# buff_n_Blend.net
KiCad netlist of a schematic drawn in EAGLE
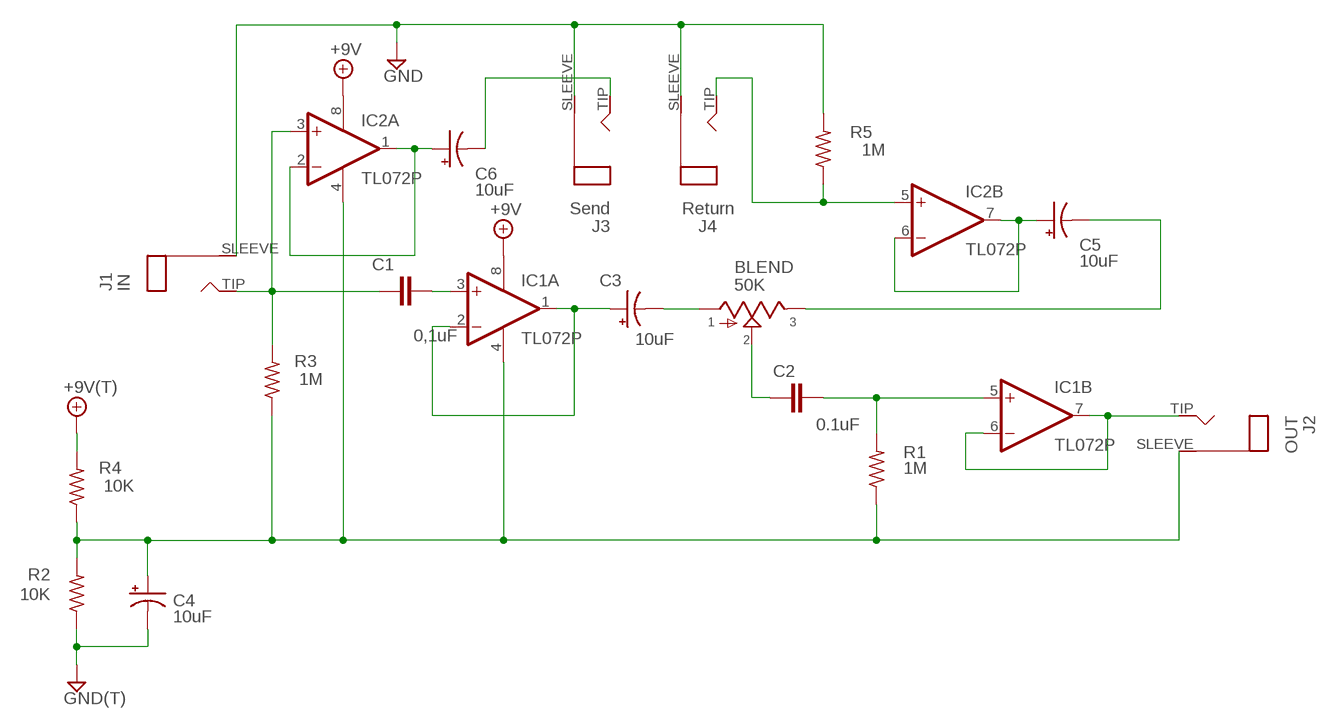
[diagram p0: schematic, sheet 1]

(export (version "E")
  (design (tool "Eeschema 10.0.6"))
  (components
    (comp (ref "+9V1")
      (value "+9V(T)")
      (footprint "eagle-import:SQUARE")
      (libsource (lib "eagle-import") (part "+9V(T)"))
    )
    (comp (ref "BLEND")
      (value "50K")
      (footprint "eagle-import:16MM")
      (libsource (lib "eagle-import") (part "POT16MM"))
    )
    (comp (ref "C1")
      (value "0,1uF")
      (footprint "eagle-import:070X030_4")
      (libsource (lib "eagle-import") (part "070X0304"))
    )
    (comp (ref "C2")
      (value "0.1uF")
      (footprint "eagle-import:070X030_4")
      (libsource (lib "eagle-import") (part "070X0304"))
    )
    (comp (ref "C3")
      (value "10uF")
      (footprint "eagle-import:063_025_3")
      (libsource (lib "eagle-import") (part "0633"))
    )
    (comp (ref "C4")
      (value "10uF")
      (footprint "eagle-import:063_025_3")
      (libsource (lib "eagle-import") (part "0633"))
    )
    (comp (ref "C5")
      (value "10uF")
      (footprint "eagle-import:063_025_3")
      (libsource (lib "eagle-import") (part "0633"))
    )
    (comp (ref "C6")
      (value "10uF")
      (footprint "eagle-import:063_025_3")
      (libsource (lib "eagle-import") (part "0633"))
    )
    (comp (ref "GND1")
      (value "GND(T)")
      (footprint "eagle-import:SQUARE")
      (libsource (lib "eagle-import") (part "GND(T)"))
    )
    (comp (ref "IC1")
      (value "TL072P")
      (footprint "eagle-import:DIL08")
      (libsource (lib "eagle-import") (part "TL072P"))
    )
    (comp (ref "IC2")
      (value "TL072P")
      (footprint "eagle-import:DIL08")
      (libsource (lib "eagle-import") (part "TL072P"))
    )
    (comp (ref "J1")
      (value "IN")
      (footprint "eagle-import:MONO_JACK")
      (libsource (lib "eagle-import") (part "MONO"))
    )
    (comp (ref "J2")
      (value "OUT")
      (footprint "eagle-import:MONO_JACK")
      (libsource (lib "eagle-import") (part "MONO"))
    )
    (comp (ref "J3")
      (value "Send")
      (footprint "eagle-import:MONO_JACK")
      (libsource (lib "eagle-import") (part "MONO"))
    )
    (comp (ref "J4")
      (value "Return")
      (footprint "eagle-import:MONO_JACK")
      (libsource (lib "eagle-import") (part "MONO"))
    )
    (comp (ref "R1")
      (value "1M")
      (footprint "eagle-import:R0207_5")
      (libsource (lib "eagle-import") (part "6MM.5"))
    )
    (comp (ref "R2")
      (value "10K")
      (footprint "eagle-import:R0207_5")
      (libsource (lib "eagle-import") (part "6MM.5"))
    )
    (comp (ref "R3")
      (value "1M")
      (footprint "eagle-import:R0207_5")
      (libsource (lib "eagle-import") (part "6MM.5"))
    )
    (comp (ref "R4")
      (value "10K")
      (footprint "eagle-import:R0207_5")
      (libsource (lib "eagle-import") (part "6MM.5"))
    )
    (comp (ref "R5")
      (value "1M")
      (footprint "eagle-import:R0207_5")
      (libsource (lib "eagle-import") (part "6MM.5"))
    )
  )
  (nets
    (net (code "1") (name "+9V") (class "Default")
      (node (ref "+9V1") (pin "1") (pinfunction "+9V_1") (pintype "power_in"))
      (node (ref "IC1") (pin "8") (pinfunction "V+_8") (pintype "power_in"))
      (node (ref "IC2") (pin "8") (pinfunction "V+_8") (pintype "power_in"))
      (node (ref "R4") (pin "2") (pinfunction "2_2") (pintype "passive"))
    )
    (net (code "2") (name "GND") (class "Default")
      (node (ref "C4") (pin "-") (pinfunction "-_-") (pintype "passive"))
      (node (ref "GND1") (pin "1") (pinfunction "GND_1") (pintype "power_in"))
      (node (ref "J1") (pin "SLEEVE") (pinfunction "SLEEVE_SLEEVE") (pintype "passive"))
      (node (ref "J3") (pin "SLEEVE") (pinfunction "SLEEVE_SLEEVE") (pintype "passive"))
      (node (ref "J4") (pin "SLEEVE") (pinfunction "SLEEVE_SLEEVE") (pintype "passive"))
      (node (ref "R2") (pin "1") (pinfunction "1_1") (pintype "passive"))
      (node (ref "R5") (pin "2") (pinfunction "2_2") (pintype "passive"))
    )
    (net (code "3") (name "Net-(BLEND-Pad1)") (class "Default")
      (node (ref "BLEND") (pin "1") (pinfunction "1_1") (pintype "passive"))
      (node (ref "C3") (pin "-") (pinfunction "-_-") (pintype "passive"))
    )
    (net (code "4") (name "Net-(BLEND-Pad2)") (class "Default")
      (node (ref "BLEND") (pin "2") (pinfunction "2_2") (pintype "passive"))
      (node (ref "C2") (pin "1") (pinfunction "1_1") (pintype "passive"))
    )
    (net (code "5") (name "Net-(BLEND-Pad3)") (class "Default")
      (node (ref "BLEND") (pin "3") (pinfunction "3_3") (pintype "passive"))
      (node (ref "C5") (pin "-") (pinfunction "-_-") (pintype "passive"))
    )
    (net (code "6") (name "Net-(C6-Pad-)") (class "Default")
      (node (ref "C6") (pin "-") (pinfunction "-_-") (pintype "passive"))
      (node (ref "J3") (pin "TIP") (pinfunction "TIP_TIP") (pintype "passive"))
    )
    (net (code "7") (name "Net-(IC1A-+IN)") (class "Default")
      (node (ref "C1") (pin "2") (pinfunction "2_2") (pintype "passive"))
      (node (ref "IC1") (pin "3") (pinfunction "+IN_3") (pintype "input"))
    )
    (net (code "8") (name "Net-(IC1A--IN)") (class "Default")
      (node (ref "C3") (pin "+") (pinfunction "+_+") (pintype "passive"))
      (node (ref "IC1") (pin "1") (pinfunction "OUT_1") (pintype "output"))
      (node (ref "IC1") (pin "2") (pinfunction "-IN_2") (pintype "input"))
    )
    (net (code "9") (name "Net-(IC1B-+IN)") (class "Default")
      (node (ref "C2") (pin "2") (pinfunction "2_2") (pintype "passive"))
      (node (ref "IC1") (pin "5") (pinfunction "+IN_5") (pintype "input"))
      (node (ref "R1") (pin "2") (pinfunction "2_2") (pintype "passive"))
    )
    (net (code "10") (name "Net-(IC1B--IN)") (class "Default")
      (node (ref "IC1") (pin "6") (pinfunction "-IN_6") (pintype "input"))
      (node (ref "IC1") (pin "7") (pinfunction "OUT_7") (pintype "output"))
      (node (ref "J2") (pin "TIP") (pinfunction "TIP_TIP") (pintype "passive"))
    )
    (net (code "11") (name "Net-(IC1C-V-)") (class "Default")
      (node (ref "C4") (pin "+") (pinfunction "+_+") (pintype "passive"))
      (node (ref "IC1") (pin "4") (pinfunction "V-_4") (pintype "power_in"))
      (node (ref "IC2") (pin "4") (pinfunction "V-_4") (pintype "power_in"))
      (node (ref "J2") (pin "SLEEVE") (pinfunction "SLEEVE_SLEEVE") (pintype "passive"))
      (node (ref "R1") (pin "1") (pinfunction "1_1") (pintype "passive"))
      (node (ref "R2") (pin "2") (pinfunction "2_2") (pintype "passive"))
      (node (ref "R3") (pin "1") (pinfunction "1_1") (pintype "passive"))
      (node (ref "R4") (pin "1") (pinfunction "1_1") (pintype "passive"))
    )
    (net (code "12") (name "Net-(IC2A-+IN)") (class "Default")
      (node (ref "C1") (pin "1") (pinfunction "1_1") (pintype "passive"))
      (node (ref "IC2") (pin "3") (pinfunction "+IN_3") (pintype "input"))
      (node (ref "J1") (pin "TIP") (pinfunction "TIP_TIP") (pintype "passive"))
      (node (ref "R3") (pin "2") (pinfunction "2_2") (pintype "passive"))
    )
    (net (code "13") (name "Net-(IC2A--IN)") (class "Default")
      (node (ref "C6") (pin "+") (pinfunction "+_+") (pintype "passive"))
      (node (ref "IC2") (pin "1") (pinfunction "OUT_1") (pintype "output"))
      (node (ref "IC2") (pin "2") (pinfunction "-IN_2") (pintype "input"))
    )
    (net (code "14") (name "Net-(IC2B-+IN)") (class "Default")
      (node (ref "IC2") (pin "5") (pinfunction "+IN_5") (pintype "input"))
      (node (ref "J4") (pin "TIP") (pinfunction "TIP_TIP") (pintype "passive"))
      (node (ref "R5") (pin "1") (pinfunction "1_1") (pintype "passive"))
    )
    (net (code "15") (name "Net-(IC2B--IN)") (class "Default")
      (node (ref "C5") (pin "+") (pinfunction "+_+") (pintype "passive"))
      (node (ref "IC2") (pin "6") (pinfunction "-IN_6") (pintype "input"))
      (node (ref "IC2") (pin "7") (pinfunction "OUT_7") (pintype "output"))
    )
  )
)
